# U_I_Meter_TOP.net
KiCad netlist of a schematic drawn in Altium Designer
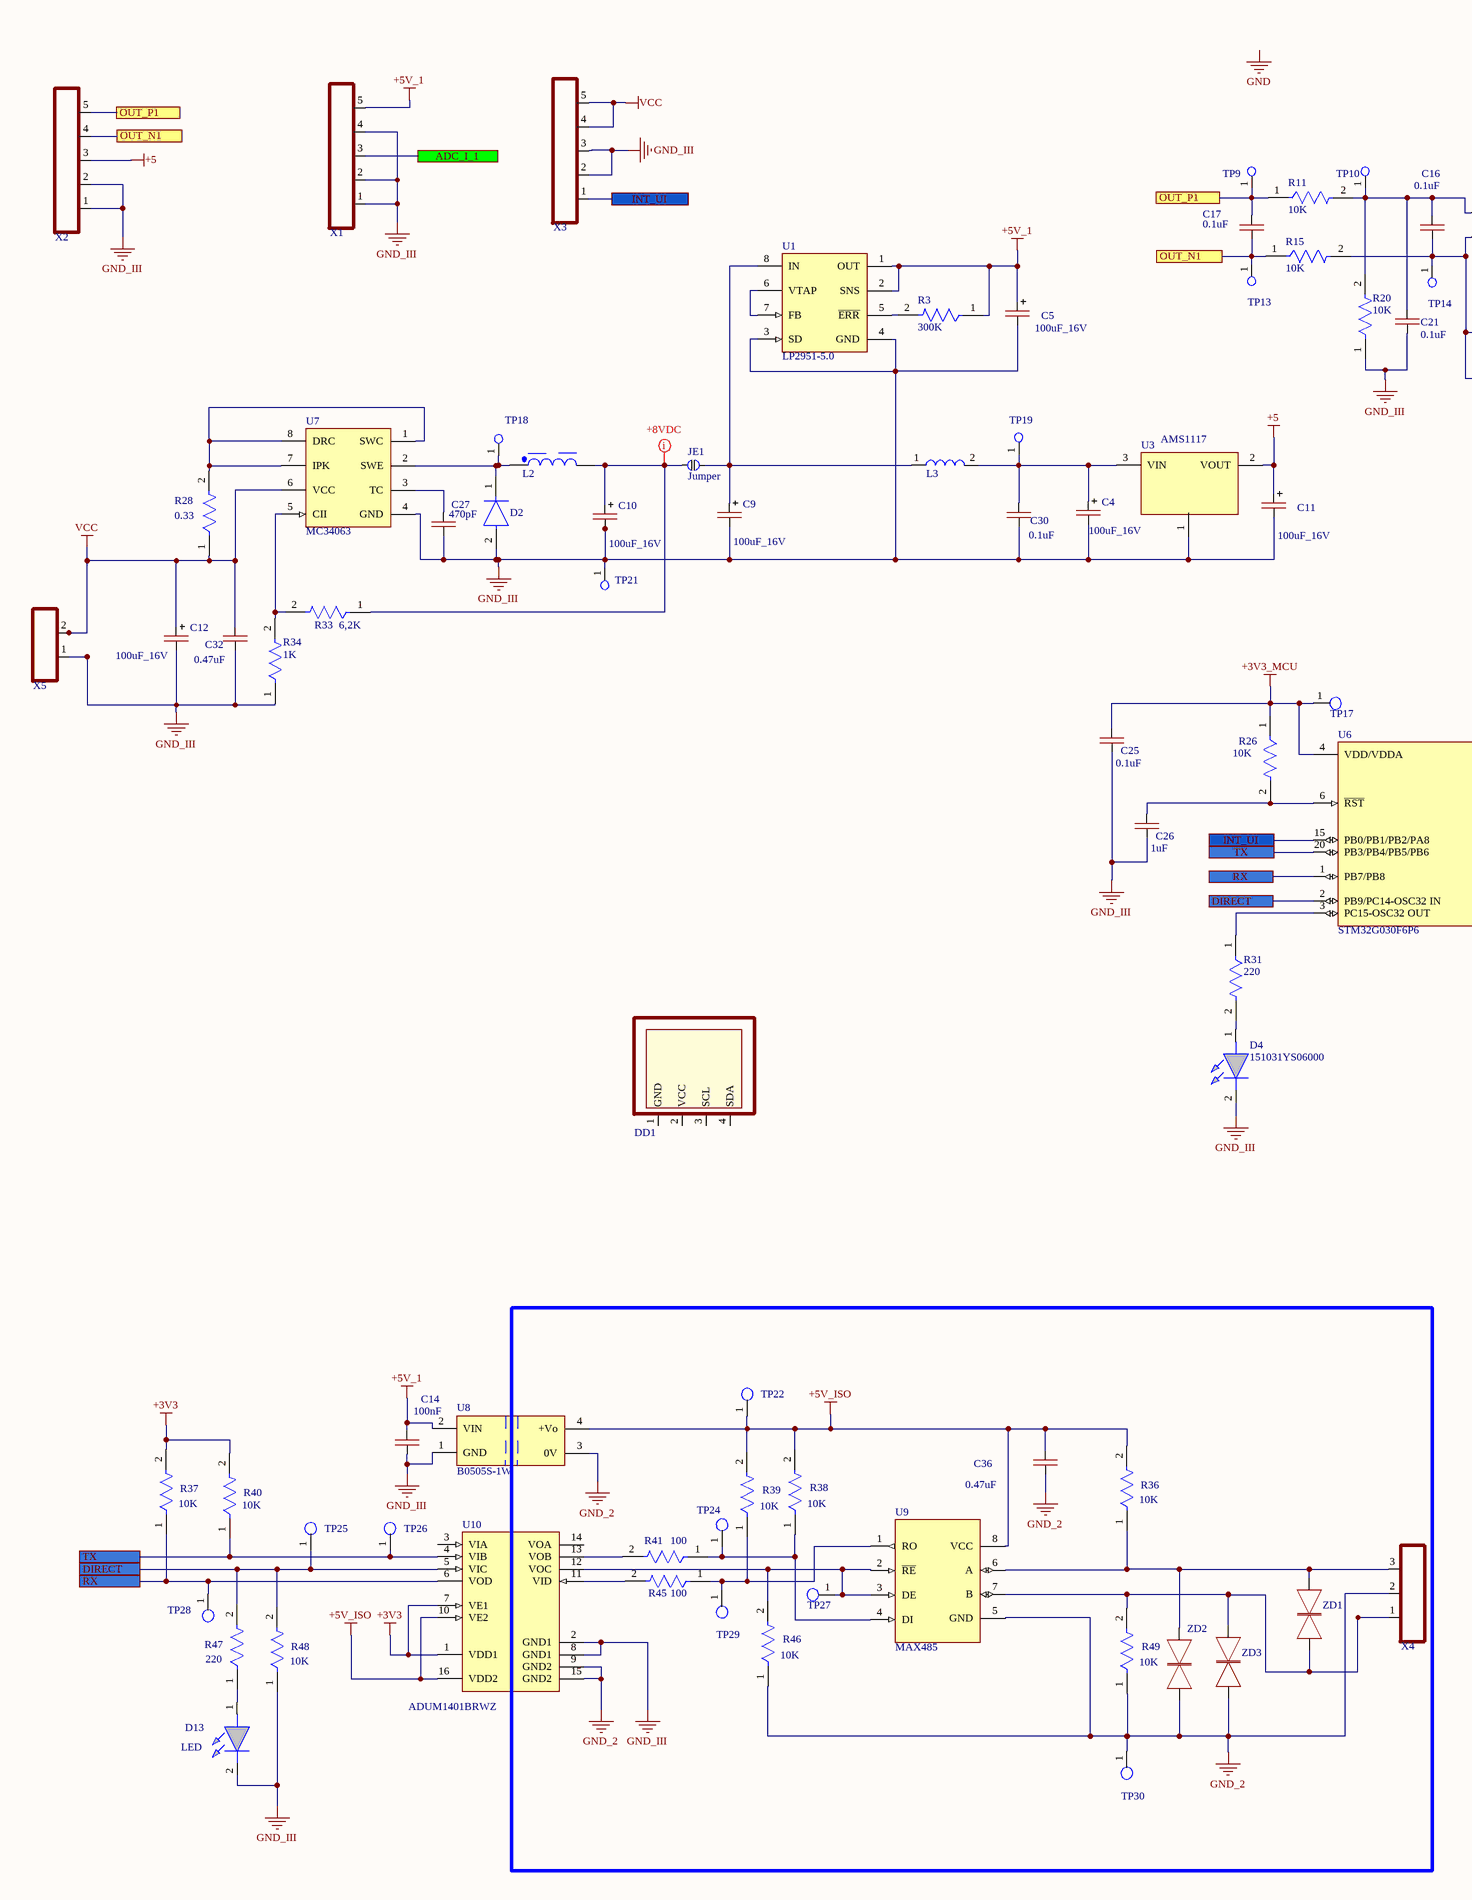
[diagram p0: U_I_Meter_TOP.SchDoc, left]
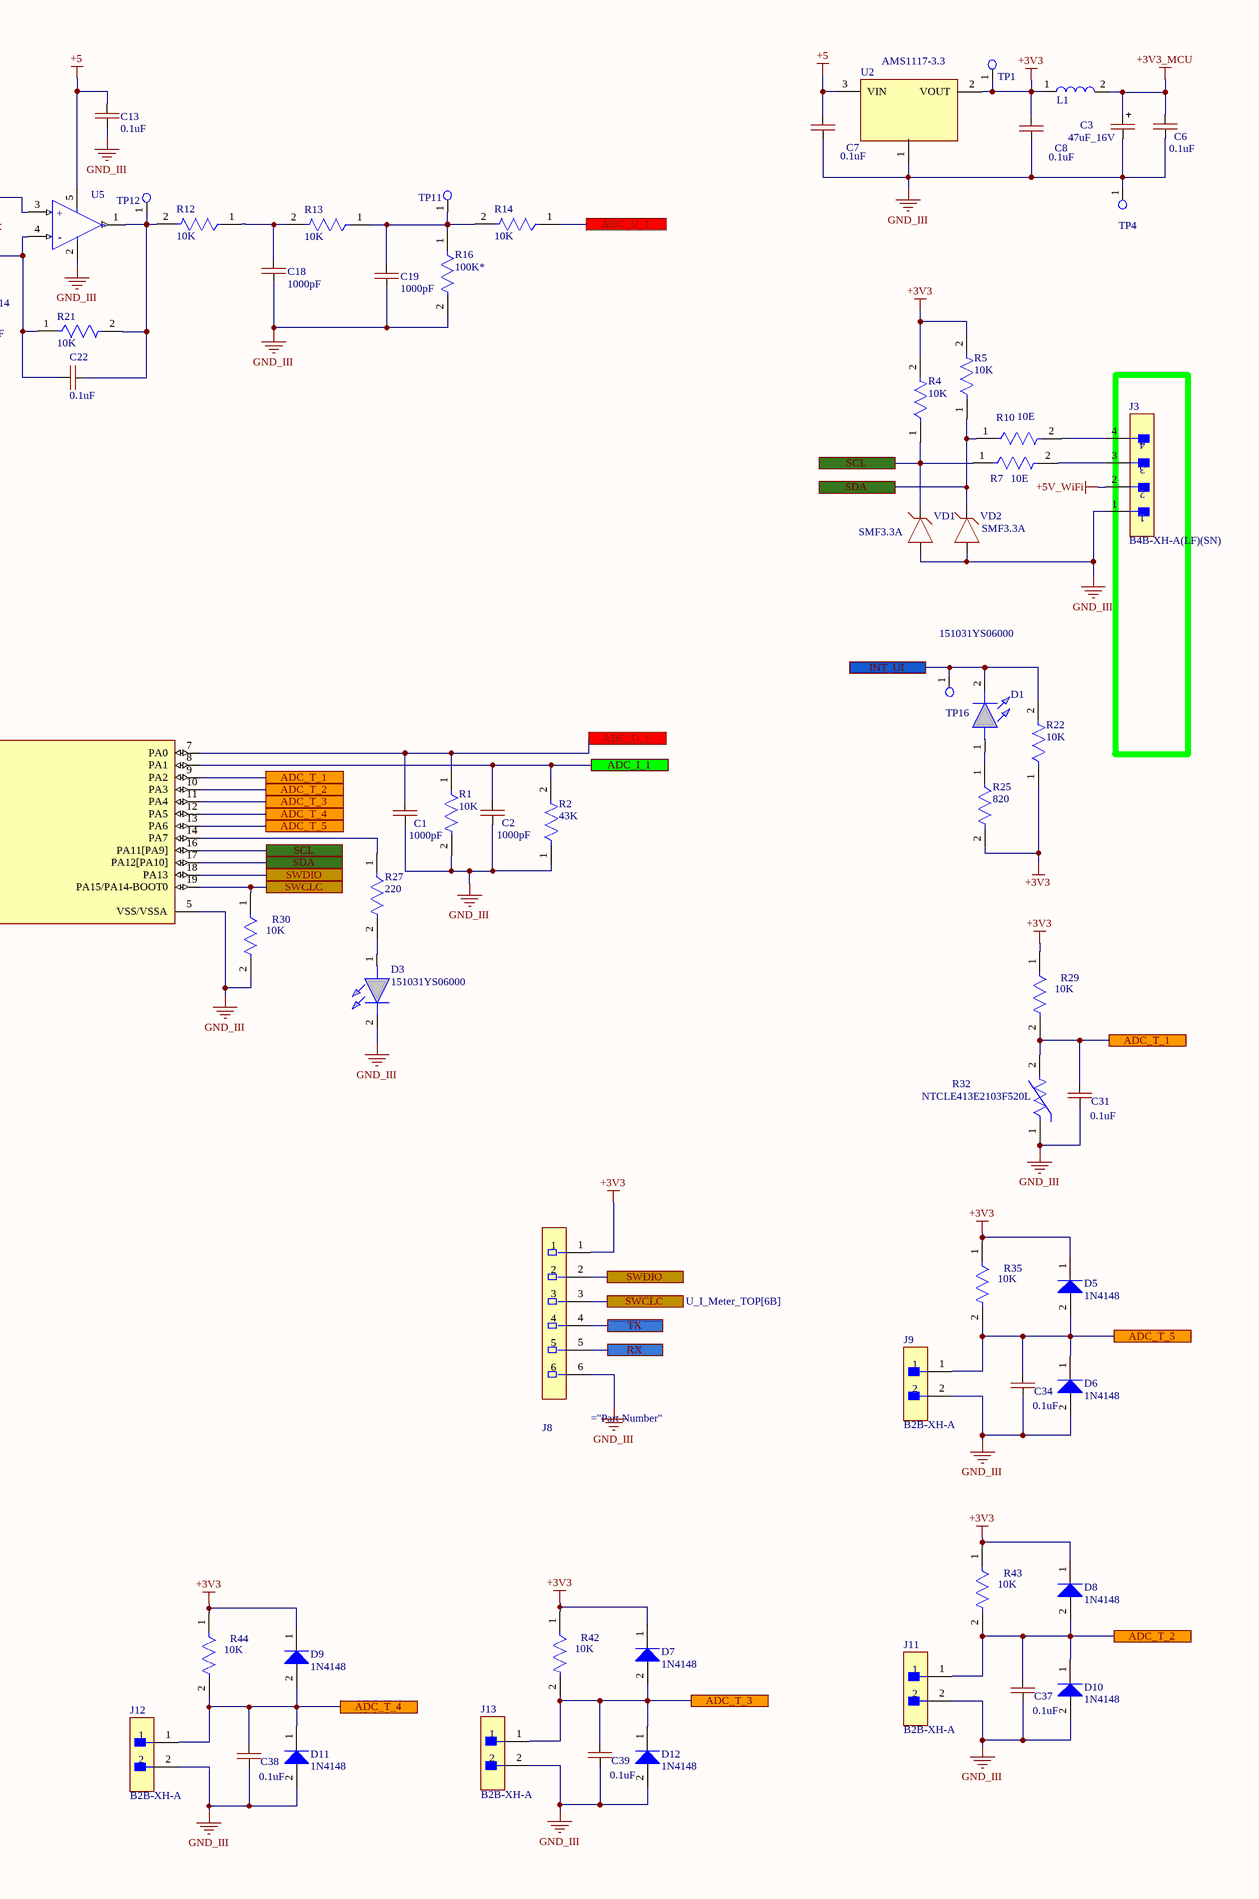
[diagram p1: U_I_Meter_TOP.SchDoc, right]

(export (version "E")
  (design (tool "Eeschema 10.0.6"))
  (components
    (comp (ref "C1")
      (value "1000pF")
      (footprint "CAP-0805")
      (libsource (lib "PASSIVE_COMPONENTS") (part "CAP-NON-POLAR"))
    )
    (comp (ref "C2")
      (value "1000pF")
      (footprint "CAP-0805")
      (libsource (lib "PASSIVE_COMPONENTS") (part "CAP-NON-POLAR"))
    )
    (comp (ref "C3")
      (value "47uF_16V")
      (footprint "CAP-TAN-D")
      (libsource (lib "PASSIVE_COMPONENTS") (part "CAP-POLAR"))
    )
    (comp (ref "C4")
      (value "100uF_16V")
      (footprint "CAP-TAN-D")
      (libsource (lib "PASSIVE_COMPONENTS") (part "CAP_POL_SMD"))
    )
    (comp (ref "C5")
      (value "100uF_16V")
      (footprint "CAP-TAN-D")
      (libsource (lib "PASSIVE_COMPONENTS") (part "CAP_POL_SMD"))
    )
    (comp (ref "C6")
      (value "0.1uF")
      (footprint "CAP-0805")
      (libsource (lib "PASSIVE_COMPONENTS") (part "CAP-NON-POLAR"))
    )
    (comp (ref "C7")
      (value "0.1uF")
      (footprint "CAP-0805")
      (libsource (lib "PASSIVE_COMPONENTS") (part "CAP-NON-POLAR"))
    )
    (comp (ref "C8")
      (value "0.1uF")
      (footprint "CAP-0805")
      (libsource (lib "PASSIVE_COMPONENTS") (part "CAP-NON-POLAR"))
    )
    (comp (ref "C9")
      (value "100uF_16V")
      (footprint "CAP-TAN-D")
      (libsource (lib "PASSIVE_COMPONENTS") (part "CAP_POL_SMD"))
    )
    (comp (ref "C10")
      (value "100uF_16V")
      (footprint "CAP-TAN-D")
      (libsource (lib "PASSIVE_COMPONENTS") (part "CAP_POL_SMD"))
    )
    (comp (ref "C11")
      (value "100uF_16V")
      (footprint "CAP-TAN-D")
      (libsource (lib "PASSIVE_COMPONENTS") (part "CAP_POL_SMD"))
    )
    (comp (ref "C12")
      (value "100uF_16V")
      (footprint "CAP-TAN-D")
      (libsource (lib "PASSIVE_COMPONENTS") (part "CAP_POL_SMD"))
    )
    (comp (ref "C13")
      (value "0.1uF")
      (footprint "CAP-0805")
      (libsource (lib "PASSIVE_COMPONENTS") (part "CAP-NON-POLAR"))
    )
    (comp (ref "C14")
      (value "100nF")
      (footprint "CAP-0805")
      (libsource (lib "PASSIVE_COMPONENTS") (part "CAP-NON-POLAR"))
    )
    (comp (ref "C16")
      (value "0.1uF")
      (footprint "CAP-0805")
      (libsource (lib "PASSIVE_COMPONENTS") (part "CAP-NON-POLAR"))
    )
    (comp (ref "C17")
      (value "0.1uF")
      (footprint "CAP-0805")
      (libsource (lib "PASSIVE_COMPONENTS") (part "CAP-NON-POLAR"))
    )
    (comp (ref "C18")
      (value "1000pF")
      (footprint "CAP-0805")
      (libsource (lib "PASSIVE_COMPONENTS") (part "CAP-NON-POLAR"))
    )
    (comp (ref "C19")
      (value "1000pF")
      (footprint "CAP-0805")
      (libsource (lib "PASSIVE_COMPONENTS") (part "CAP-NON-POLAR"))
    )
    (comp (ref "C21")
      (value "0.1uF")
      (footprint "CAP-0805")
      (libsource (lib "PASSIVE_COMPONENTS") (part "CAP-NON-POLAR"))
    )
    (comp (ref "C22")
      (value "0.1uF")
      (footprint "CAP-0805")
      (libsource (lib "PASSIVE_COMPONENTS") (part "CAP-NON-POLAR"))
    )
    (comp (ref "C25")
      (value "0.1uF")
      (footprint "CAP-0805")
      (libsource (lib "PASSIVE_COMPONENTS") (part "CAP-NON-POLAR"))
    )
    (comp (ref "C26")
      (value "1uF")
      (footprint "CAP-0805")
      (libsource (lib "PASSIVE_COMPONENTS") (part "CAP-NON-POLAR"))
    )
    (comp (ref "C27")
      (value "470pF")
      (footprint "CAP-0805")
      (libsource (lib "PASSIVE_COMPONENTS") (part "CAP-NON-POLAR"))
    )
    (comp (ref "C30")
      (value "0.1uF")
      (footprint "CAP-0805")
      (libsource (lib "PASSIVE_COMPONENTS") (part "CAP-NON-POLAR"))
    )
    (comp (ref "C31")
      (value "0.1uF")
      (footprint "CAP-0805")
      (libsource (lib "PASSIVE_COMPONENTS") (part "CAP-NON-POLAR"))
    )
    (comp (ref "C32")
      (value "0.47uF")
      (footprint "CAP-0805")
      (libsource (lib "PASSIVE_COMPONENTS") (part "CAP-NON-POLAR"))
    )
    (comp (ref "C34")
      (value "0.1uF")
      (footprint "CAP-0805")
      (libsource (lib "PASSIVE_COMPONENTS") (part "CAP-NON-POLAR"))
    )
    (comp (ref "C36")
      (value "0.47uF")
      (footprint "CAP-0805")
      (libsource (lib "PASSIVE_COMPONENTS") (part "CAP-NON-POLAR"))
    )
    (comp (ref "C37")
      (value "0.1uF")
      (footprint "CAP-0805")
      (libsource (lib "PASSIVE_COMPONENTS") (part "CAP-NON-POLAR"))
    )
    (comp (ref "C38")
      (value "0.1uF")
      (footprint "CAP-0805")
      (libsource (lib "PASSIVE_COMPONENTS") (part "CAP-NON-POLAR"))
    )
    (comp (ref "C39")
      (value "0.1uF")
      (footprint "CAP-0805")
      (libsource (lib "PASSIVE_COMPONENTS") (part "CAP-NON-POLAR"))
    )
    (comp (ref "D1")
      (value "151031YS06000")
      (footprint "LED_3mm_BLUE")
      (description "WURTH ELEKTRONIK - 151031YS06000 - LED, Yellow, Through Hole, T-1 (3mm), 30 mA, 2 V, 590 nm")
      (fields (field (name "MOUSER PART NUMBER") "710-151031YS06000"))
      (libsource (lib "Optic-LED") (part "LED"))
    )
    (comp (ref "D2")
      (value "ES1G")
      (footprint "FP-403AE-MFG")
      (description "Ultrafast")
      (libsource (lib "Diodes") (part "ES1G"))
    )
    (comp (ref "D3")
      (value "151031YS06000")
      (footprint "LED_3mm_GREEN")
      (description "WURTH ELEKTRONIK - 151031YS06000 - LED, Yellow, Through Hole, T-1 (3mm), 30 mA, 2 V, 590 nm")
      (fields (field (name "MOUSER PART NUMBER") "710-151031YS06000"))
      (libsource (lib "Optic-LED") (part "LED"))
    )
    (comp (ref "D4")
      (value "151031YS06000")
      (footprint "LED_3mm_RED")
      (description "WURTH ELEKTRONIK - 151031YS06000 - LED, Yellow, Through Hole, T-1 (3mm), 30 mA, 2 V, 590 nm")
      (fields (field (name "MOUSER PART NUMBER") "710-151031YS06000"))
      (libsource (lib "Optic-LED") (part "LED"))
    )
    (comp (ref "D5")
      (value "1N4148")
      (footprint "DIOD-SOD123-2_V")
      (libsource (lib "Diodes") (part "1N4148"))
    )
    (comp (ref "D6")
      (value "1N4148")
      (footprint "DIOD-SOD123-2_V")
      (libsource (lib "Diodes") (part "1N4148"))
    )
    (comp (ref "D7")
      (value "1N4148")
      (footprint "DIOD-SOD123-2_V")
      (libsource (lib "Diodes") (part "1N4148"))
    )
    (comp (ref "D8")
      (value "1N4148")
      (footprint "DIOD-SOD123-2_V")
      (libsource (lib "Diodes") (part "1N4148"))
    )
    (comp (ref "D9")
      (value "1N4148")
      (footprint "DIOD-SOD123-2_V")
      (libsource (lib "Diodes") (part "1N4148"))
    )
    (comp (ref "D10")
      (value "1N4148")
      (footprint "DIOD-SOD123-2_V")
      (libsource (lib "Diodes") (part "1N4148"))
    )
    (comp (ref "D11")
      (value "1N4148")
      (footprint "DIOD-SOD123-2_V")
      (libsource (lib "Diodes") (part "1N4148"))
    )
    (comp (ref "D12")
      (value "1N4148")
      (footprint "DIOD-SOD123-2_V")
      (libsource (lib "Diodes") (part "1N4148"))
    )
    (comp (ref "D13")
      (value "LED")
      (footprint "LED_3mm_BLUE")
      (description "WURTH ELEKTRONIK - 151031YS06000 - LED, Yellow, Through Hole, T-1 (3mm), 30 mA, 2 V, 590 nm")
      (fields
        (field (name "MANUFACTURER_PART_NUMBER") "151031YS06000")
        (field (name "MOUSER PART NUMBER") "710-151031YS06000")
      )
      (libsource (lib "Optic-LED") (part "LED"))
    )
    (comp (ref "DD1")
      (value "OLED_SSD_1306")
      (footprint "OLED_128x64_SSD_1306")
      (libsource (lib "Displays") (part "OLED_SSD_1306"))
    )
    (comp (ref "J3")
      (value "B4B-XH-A(LF)(SN)")
      (footprint "B4B-XH-A")
      (libsource (lib "Connectors") (part "B4B-XH-A(LF)(SN)"))
    )
    (comp (ref "J8")
      (value "SWR25X-NRTC-S06-ST-BA")
      (footprint "Sullins_SWR25X-NRTC-S06-ST-BA_MFG")
      (libsource (lib "Conn_Sullins_SWR25X-NRTC-S06-ST-BA_eec") (part "SWR25X-NRTC-S06-ST-BA"))
    )
    (comp (ref "J9")
      (value "B2B-XH-A")
      (footprint "B2B-XH-A")
      (libsource (lib "Connectors") (part "B2B-XH-A"))
    )
    (comp (ref "J11")
      (value "B2B-XH-A")
      (footprint "B2B-XH-A")
      (libsource (lib "Connectors") (part "B2B-XH-A"))
    )
    (comp (ref "J12")
      (value "B2B-XH-A")
      (footprint "B2B-XH-A")
      (libsource (lib "Connectors") (part "B2B-XH-A"))
    )
    (comp (ref "J13")
      (value "B2B-XH-A")
      (footprint "B2B-XH-A")
      (libsource (lib "Connectors") (part "B2B-XH-A"))
    )
    (comp (ref "JE1") (value "Jumper") (footprint "JE") (libsource (lib "Connectors") (part "JE")))
    (comp (ref "L1")
      (value "Coil")
      (footprint "Coil_4.5x4.5_mm")
      (libsource (lib "Transformers") (part "Coil"))
    )
    (comp (ref "L2")
      (value "3.3µH, 4A")
      (footprint "WE-PD2_5848")
      (description "WE-PD2 SMT Power Inductor, size 5848, 3.3µH, 4A, 0.06Ω")
      (fields
        (field (name "MANUFACTURER PART NUMBER") "744774033")
        (field (name "MANUFACTURER") "Wurth Elektronik")
      )
      (libsource (lib "WE-PD2 (rev22d)") (part "744774033"))
    )
    (comp (ref "L3")
      (value "Coil")
      (footprint "Coil_4.5x4.5_mm")
      (libsource (lib "Transformers") (part "Coil"))
    )
    (comp (ref "R1")
      (value "10K")
      (footprint "RES-0805")
      (libsource (lib "PASSIVE_COMPONENTS") (part "RES-CONST"))
    )
    (comp (ref "R2")
      (value "43K")
      (footprint "RES-0805")
      (libsource (lib "PASSIVE_COMPONENTS") (part "RES-CONST"))
    )
    (comp (ref "R3")
      (value "300K")
      (footprint "RES-0805")
      (libsource (lib "PASSIVE_COMPONENTS") (part "RES-CONST"))
    )
    (comp (ref "R4")
      (value "10K")
      (footprint "RES-0805")
      (libsource (lib "PASSIVE_COMPONENTS") (part "RES-CONST"))
    )
    (comp (ref "R5")
      (value "10K")
      (footprint "RES-0805")
      (libsource (lib "PASSIVE_COMPONENTS") (part "RES-CONST"))
    )
    (comp (ref "R7")
      (value "10E")
      (footprint "RES-0805")
      (libsource (lib "PASSIVE_COMPONENTS") (part "RES-CONST"))
    )
    (comp (ref "R10")
      (value "10E")
      (footprint "RES-0805")
      (libsource (lib "PASSIVE_COMPONENTS") (part "RES-CONST"))
    )
    (comp (ref "R11")
      (value "10K")
      (footprint "RES-0805")
      (libsource (lib "PASSIVE_COMPONENTS") (part "RES-CONST"))
    )
    (comp (ref "R12")
      (value "10K")
      (footprint "RES-0805")
      (libsource (lib "PASSIVE_COMPONENTS") (part "RES-CONST"))
    )
    (comp (ref "R13")
      (value "10K")
      (footprint "RES-0805")
      (libsource (lib "PASSIVE_COMPONENTS") (part "RES-CONST"))
    )
    (comp (ref "R14")
      (value "10K")
      (footprint "RES-0805")
      (libsource (lib "PASSIVE_COMPONENTS") (part "RES-CONST"))
    )
    (comp (ref "R15")
      (value "10K")
      (footprint "RES-0805")
      (libsource (lib "PASSIVE_COMPONENTS") (part "RES-CONST"))
    )
    (comp (ref "R16")
      (value "100K*")
      (footprint "RES-0805")
      (libsource (lib "PASSIVE_COMPONENTS") (part "RES-CONST"))
    )
    (comp (ref "R20")
      (value "10K")
      (footprint "RES-0805")
      (libsource (lib "PASSIVE_COMPONENTS") (part "RES-CONST"))
    )
    (comp (ref "R21")
      (value "10K")
      (footprint "RES-0805")
      (libsource (lib "PASSIVE_COMPONENTS") (part "RES-CONST"))
    )
    (comp (ref "R22")
      (value "10K")
      (footprint "RES-0805")
      (libsource (lib "PASSIVE_COMPONENTS") (part "RES-CONST"))
    )
    (comp (ref "R25")
      (value "820")
      (footprint "RES-0805")
      (description "220")
      (libsource (lib "PASSIVE_COMPONENTS") (part "RES-CONST"))
    )
    (comp (ref "R26")
      (value "10K")
      (footprint "RES-0805")
      (libsource (lib "PASSIVE_COMPONENTS") (part "RES-CONST"))
    )
    (comp (ref "R27")
      (value "220")
      (footprint "RES-0805")
      (libsource (lib "PASSIVE_COMPONENTS") (part "RES-CONST"))
    )
    (comp (ref "R28")
      (value "0.33")
      (footprint "RES-1206")
      (libsource (lib "PASSIVE_COMPONENTS") (part "RES-CONST"))
    )
    (comp (ref "R29")
      (value "10K")
      (footprint "RES-0805")
      (libsource (lib "PASSIVE_COMPONENTS") (part "RES-CONST"))
    )
    (comp (ref "R30")
      (value "10K")
      (footprint "RES-0805")
      (libsource (lib "PASSIVE_COMPONENTS") (part "RES-CONST"))
    )
    (comp (ref "R31")
      (value "220")
      (footprint "RES-0805")
      (libsource (lib "PASSIVE_COMPONENTS") (part "RES-CONST"))
    )
    (comp (ref "R32")
      (value "NTCLE413E2103F520L")
      (footprint "FP-NTCLE413E2103F520L-MFG")
      (description "THERMISTOR NTC 10KOHM 3435K BEAD")
      (fields (field (name "TOLERANCE") "1%"))
      (libsource (lib "Altium Content Vault") (part "3b148a6ebabc5fb4d708a66c052d352"))
    )
    (comp (ref "R33")
      (value "6,2K")
      (footprint "RES-0805")
      (description "10K")
      (libsource (lib "PASSIVE_COMPONENTS") (part "RES-CONST"))
    )
    (comp (ref "R34")
      (value "1K")
      (footprint "RES-0805")
      (description "1.2K")
      (libsource (lib "PASSIVE_COMPONENTS") (part "RES-CONST"))
    )
    (comp (ref "R35")
      (value "10K")
      (footprint "RES-0805")
      (libsource (lib "PASSIVE_COMPONENTS") (part "RES-CONST"))
    )
    (comp (ref "R36")
      (value "10K")
      (footprint "RES-0805")
      (libsource (lib "PASSIVE_COMPONENTS") (part "RES-CONST"))
    )
    (comp (ref "R37")
      (value "10K")
      (footprint "RES-0805")
      (libsource (lib "PASSIVE_COMPONENTS") (part "RES-CONST"))
    )
    (comp (ref "R38")
      (value "10K")
      (footprint "RES-0805")
      (libsource (lib "PASSIVE_COMPONENTS") (part "RES-CONST"))
    )
    (comp (ref "R39")
      (value "10K")
      (footprint "RES-0805")
      (libsource (lib "PASSIVE_COMPONENTS") (part "RES-CONST"))
    )
    (comp (ref "R40")
      (value "10K")
      (footprint "RES-0805")
      (libsource (lib "PASSIVE_COMPONENTS") (part "RES-CONST"))
    )
    (comp (ref "R41")
      (value "100")
      (footprint "RES-0805")
      (libsource (lib "PASSIVE_COMPONENTS") (part "RES-CONST"))
    )
    (comp (ref "R42")
      (value "10K")
      (footprint "RES-0805")
      (libsource (lib "PASSIVE_COMPONENTS") (part "RES-CONST"))
    )
    (comp (ref "R43")
      (value "10K")
      (footprint "RES-0805")
      (libsource (lib "PASSIVE_COMPONENTS") (part "RES-CONST"))
    )
    (comp (ref "R44")
      (value "10K")
      (footprint "RES-0805")
      (libsource (lib "PASSIVE_COMPONENTS") (part "RES-CONST"))
    )
    (comp (ref "R45")
      (value "100")
      (footprint "RES-0805")
      (libsource (lib "PASSIVE_COMPONENTS") (part "RES-CONST"))
    )
    (comp (ref "R46")
      (value "10K")
      (footprint "RES-0805")
      (libsource (lib "PASSIVE_COMPONENTS") (part "RES-CONST"))
    )
    (comp (ref "R47")
      (value "220")
      (footprint "RES-0805")
      (libsource (lib "PASSIVE_COMPONENTS") (part "RES-CONST"))
    )
    (comp (ref "R48")
      (value "10K")
      (footprint "RES-0805")
      (libsource (lib "PASSIVE_COMPONENTS") (part "RES-CONST"))
    )
    (comp (ref "R49")
      (value "10K")
      (footprint "RES-0805")
      (libsource (lib "PASSIVE_COMPONENTS") (part "RES-CONST"))
    )
    (comp (ref "TP1")
      (value "Test_Point_PCB")
      (footprint "Test_Point")
      (description "Test_Point")
      (libsource (lib "Connectors") (part "TP_PCB?"))
    )
    (comp (ref "TP4")
      (value "Test_Point_PCB")
      (footprint "Pin_Test_Point(Pink)")
      (description "Test_Point")
      (libsource (lib "Connectors") (part "TP_PCB?"))
    )
    (comp (ref "TP9")
      (value "Test_Point_PCB")
      (footprint "Test_Point")
      (description "Test_Point")
      (libsource (lib "Connectors") (part "TP_PCB?"))
    )
    (comp (ref "TP10")
      (value "Test_Point_PCB")
      (footprint "Test_Point")
      (description "Test_Point")
      (libsource (lib "Connectors") (part "TP_PCB?"))
    )
    (comp (ref "TP11")
      (value "Test_Point_PCB")
      (footprint "Test_Point")
      (description "Test_Point")
      (libsource (lib "Connectors") (part "TP_PCB?"))
    )
    (comp (ref "TP12")
      (value "Test_Point_PCB")
      (footprint "Test_Point")
      (description "Test_Point")
      (libsource (lib "Connectors") (part "TP_PCB?"))
    )
    (comp (ref "TP13")
      (value "Test_Point_PCB")
      (footprint "Test_Point")
      (description "Test_Point")
      (libsource (lib "Connectors") (part "TP_PCB?"))
    )
    (comp (ref "TP14")
      (value "Test_Point_PCB")
      (footprint "Test_Point")
      (description "Test_Point")
      (libsource (lib "Connectors") (part "TP_PCB?"))
    )
    (comp (ref "TP16")
      (value "Test_Point_PCB")
      (footprint "Test_Point")
      (description "Test_Point")
      (libsource (lib "Connectors") (part "TP_PCB?"))
    )
    (comp (ref "TP17")
      (value "~")
      (footprint "Test_Point")
      (description "Test_Point")
      (libsource (lib "") (part "TP_PCB?_1"))
    )
    (comp (ref "TP18")
      (value "Test_Point_PCB")
      (footprint "Test_Point")
      (description "Test_Point")
      (libsource (lib "Connectors") (part "TP_PCB?"))
    )
    (comp (ref "TP19")
      (value "Test_Point_PCB")
      (footprint "Test_Point")
      (description "Test_Point")
      (libsource (lib "Connectors") (part "TP_PCB?"))
    )
    (comp (ref "TP21")
      (value "Test_Point_PCB")
      (footprint "Pin_Test_Point(Orange)")
      (description "Test_Point")
      (libsource (lib "Connectors") (part "TP_PCB?"))
    )
    (comp (ref "TP22")
      (value "Test_Point_PCB")
      (footprint "Test_Point")
      (description "Test_Point")
      (libsource (lib "Test_Point") (part "TP_PCB?"))
    )
    (comp (ref "TP24")
      (value "Test_Point_PCB")
      (footprint "Test_Point")
      (description "Test_Point")
      (libsource (lib "Test_Point") (part "TP_PCB?"))
    )
    (comp (ref "TP25")
      (value "Test_Point_PCB")
      (footprint "Test_Point")
      (description "Test_Point")
      (libsource (lib "Test_Point") (part "TP_PCB?"))
    )
    (comp (ref "TP26")
      (value "Test_Point_PCB")
      (footprint "Test_Point")
      (description "Test_Point")
      (libsource (lib "Test_Point") (part "TP_PCB?"))
    )
    (comp (ref "TP27")
      (value "Test_Point_PCB")
      (footprint "Test_Point")
      (description "Test_Point")
      (libsource (lib "Test_Point") (part "TP_PCB?"))
    )
    (comp (ref "TP28")
      (value "Test_Point_PCB")
      (footprint "Test_Point")
      (description "Test_Point")
      (libsource (lib "Test_Point") (part "TP_PCB?"))
    )
    (comp (ref "TP29")
      (value "~")
      (footprint "Test_Point")
      (description "Test_Point")
      (libsource (lib "") (part "TP_PCB?_1"))
    )
    (comp (ref "TP30")
      (value "Test_Point_PCB")
      (footprint "Test_Point")
      (description "Test_Point")
      (libsource (lib "Test_Point") (part "TP_PCB?"))
    )
    (comp (ref "U1")
      (value "LP2951-5.0")
      (footprint "SOIC-8_L")
      (libsource (lib "Integrated_Circuts") (part "LP2951-3.3"))
    )
    (comp (ref "U2")
      (value "AMS1117-3.3")
      (footprint "SOT-223")
      (libsource (lib "Integrated_Circuts") (part "AMS1117"))
    )
    (comp (ref "U3")
      (value "AMS1117")
      (footprint "SOT-89")
      (libsource (lib "Integrated_Circuts") (part "AMS1117"))
    )
    (comp (ref "U5")
      (value "~")
      (footprint "SOT-23-5")
      (description "IC OPAMP GP 1 CIRCUIT SOT23-5")
      (fields (field (name "VOLTAGE") "6V"))
      (libsource (lib "Integrated_Circuts") (part "MCP6001T"))
    )
    (comp (ref "U6")
      (value "STM32G030F6P6")
      (footprint "FP-TSSOP20-YA-IPC_A")
      (description "SOIC-20")
      (libsource (lib "Integrated_Circuts") (part "STM32G030F6P6"))
    )
    (comp (ref "U7")
      (value "MC34063")
      (footprint "SOIC-8_M")
      (libsource (lib "Integrated_Circuts") (part "MC34063"))
    )
    (comp (ref "U8")
      (value "B0505S-1W")
      (footprint "B0505S-1W")
      (libsource (lib "Integrated_Circuts") (part "B0505S-1W"))
    )
    (comp (ref "U9")
      (value "MAX485")
      (footprint "SOIC-8-MFG")
      (libsource (lib "Integrated_Circuts") (part "MAX485"))
    )
    (comp (ref "U10")
      (value "ADUM1401BRWZ")
      (footprint "ADI-RW-16_M")
      (fields (field (name "MANUFACTURER") "Analog Devices"))
      (libsource (lib "Altium Content Vault") (part "ADI-ADUMX4X1-16"))
    )
    (comp (ref "VD1")
      (value "SMF3.3A")
      (footprint "SMF3.3A")
      (libsource (lib "Diodes") (part "ESD_Unidirect"))
    )
    (comp (ref "VD2")
      (value "SMF3.3A")
      (footprint "SMF3.3A")
      (libsource (lib "Diodes") (part "ESD_Unidirect"))
    )
    (comp (ref "X1")
      (value "CONN-5-PIN")
      (footprint "CONN-PLS-5-2.54_2")
      (libsource (lib "PLS-5__") (part "CONN-5-PIN"))
    )
    (comp (ref "X2")
      (value "CONN-5-PIN")
      (footprint "CONN-PLS-5-2.54_2")
      (libsource (lib "PLS-5__") (part "CONN-5-PIN"))
    )
    (comp (ref "X3")
      (value "CONN-5-PIN")
      (footprint "CONN-PLS-5-2.54_2")
      (libsource (lib "PLS-5__") (part "CONN-5-PIN"))
    )
    (comp (ref "X4")
      (value "CONN-3-PIN")
      (footprint "691305340003")
      (libsource (lib "691305340003") (part "CONN-3-PIN"))
    )
    (comp (ref "X5")
      (value "CONN-2-PIN")
      (footprint "691305340002")
      (libsource (lib "691305340003") (part "CONN-2-PIN"))
    )
    (comp (ref "ZD1")
      (value "P6SMB16CA")
      (footprint "DO-214AA")
      (libsource (lib "P6SMB16CA") (part "P6SMB16CA"))
    )
    (comp (ref "ZD2")
      (value "P6SMB16CA")
      (footprint "DO-214AA")
      (libsource (lib "P6SMB16CA") (part "P6SMB16CA"))
    )
    (comp (ref "ZD3")
      (value "P6SMB16CA")
      (footprint "DO-214AA")
      (libsource (lib "P6SMB16CA") (part "P6SMB16CA"))
    )
  )
  (nets
    (net (code "1") (name "+3V3") (class "Default")
      (node (ref "C8") (pin "2") (pinfunction "2_2") (pintype "passive"))
      (node (ref "D5") (pin "1") (pinfunction "K_1") (pintype "passive"))
      (node (ref "D7") (pin "1") (pinfunction "K_1") (pintype "passive"))
      (node (ref "D8") (pin "1") (pinfunction "K_1") (pintype "passive"))
      (node (ref "D9") (pin "1") (pinfunction "K_1") (pintype "passive"))
      (node (ref "J8") (pin "1") (pinfunction "1_1") (pintype "passive"))
      (node (ref "L1") (pin "1") (pinfunction "1_1") (pintype "passive"))
      (node (ref "R22") (pin "1") (pinfunction "1_1") (pintype "passive"))
      (node (ref "R25") (pin "2") (pinfunction "2_2") (pintype "passive"))
      (node (ref "R29") (pin "1") (pinfunction "1_1") (pintype "passive"))
      (node (ref "R35") (pin "1") (pinfunction "1_1") (pintype "passive"))
      (node (ref "R37") (pin "2") (pinfunction "2_2") (pintype "passive"))
      (node (ref "R4") (pin "2") (pinfunction "2_2") (pintype "passive"))
      (node (ref "R40") (pin "2") (pinfunction "2_2") (pintype "passive"))
      (node (ref "R42") (pin "1") (pinfunction "1_1") (pintype "passive"))
      (node (ref "R43") (pin "1") (pinfunction "1_1") (pintype "passive"))
      (node (ref "R44") (pin "1") (pinfunction "1_1") (pintype "passive"))
      (node (ref "R5") (pin "2") (pinfunction "2_2") (pintype "passive"))
      (node (ref "TP1") (pin "1") (pinfunction "G9_1") (pintype "passive"))
      (node (ref "U10") (pin "1") (pinfunction "VDD1_1") (pintype "power_in"))
      (node (ref "U10") (pin "7") (pinfunction "VE1_7") (pintype "input"))
      (node (ref "U2") (pin "2") (pinfunction "VOUT_2") (pintype "passive"))
    )
    (net (code "2") (name "+3V3_MCU") (class "Default")
      (node (ref "C25") (pin "2") (pinfunction "2_2") (pintype "passive"))
      (node (ref "C3") (pin "1") (pinfunction "+_1") (pintype "passive"))
      (node (ref "C6") (pin "2") (pinfunction "2_2") (pintype "passive"))
      (node (ref "L1") (pin "2") (pinfunction "2_2") (pintype "passive"))
      (node (ref "R26") (pin "1") (pinfunction "1_1") (pintype "passive"))
      (node (ref "TP17") (pin "1") (pinfunction "G9_1") (pintype "passive"))
      (node (ref "U6") (pin "4") (pinfunction "VDD/VDDA_4") (pintype "power_in"))
    )
    (net (code "3") (name "+5") (class "Default")
      (node (ref "C11") (pin "1") (pinfunction "+_1") (pintype "passive"))
      (node (ref "C13") (pin "2") (pinfunction "2_2") (pintype "passive"))
      (node (ref "C7") (pin "2") (pinfunction "2_2") (pintype "passive"))
      (node (ref "U2") (pin "3") (pinfunction "VIN_3") (pintype "power_in"))
      (node (ref "U3") (pin "2") (pinfunction "VOUT_2") (pintype "passive"))
      (node (ref "U5") (pin "5") (pinfunction "VDD_5") (pintype "power_in"))
      (node (ref "X2") (pin "3") (pinfunction "3_3") (pintype "passive"))
    )
    (net (code "4") (name "+5V_1") (class "Default")
      (node (ref "C14") (pin "2") (pinfunction "2_2") (pintype "passive"))
      (node (ref "C5") (pin "1") (pinfunction "+_1") (pintype "passive"))
      (node (ref "R3") (pin "1") (pinfunction "1_1") (pintype "passive"))
      (node (ref "U1") (pin "1") (pinfunction "OUT_1") (pintype "power_in"))
      (node (ref "U1") (pin "2") (pinfunction "SNS_2") (pintype "passive"))
      (node (ref "U8") (pin "2") (pinfunction "VIN_2") (pintype "power_in"))
      (node (ref "X1") (pin "5") (pinfunction "5_5") (pintype "passive"))
    )
    (net (code "5") (name "+5V_ISO") (class "Default")
      (node (ref "C36") (pin "1") (pinfunction "1_1") (pintype "passive"))
      (node (ref "R36") (pin "2") (pinfunction "2_2") (pintype "passive"))
      (node (ref "R38") (pin "2") (pinfunction "2_2") (pintype "passive"))
      (node (ref "R39") (pin "2") (pinfunction "2_2") (pintype "passive"))
      (node (ref "TP22") (pin "1") (pinfunction "G9_1") (pintype "passive"))
      (node (ref "U10") (pin "10") (pinfunction "VE2_10") (pintype "input"))
      (node (ref "U10") (pin "16") (pinfunction "VDD2_16") (pintype "power_in"))
      (node (ref "U8") (pin "4") (pinfunction "+Vo_4") (pintype "power_in"))
      (node (ref "U9") (pin "8") (pinfunction "VCC_8") (pintype "power_in"))
    )
    (net (code "6") (name "+5V_WiFi") (class "Default")
      (node (ref "J3") (pin "2") (pinfunction "2_2") (pintype "passive"))
    )
    (net (code "7") (name "/ADC_I_1") (class "Default")
      (node (ref "C2") (pin "2") (pinfunction "2_2") (pintype "passive"))
      (node (ref "R2") (pin "2") (pinfunction "2_2") (pintype "passive"))
      (node (ref "U6") (pin "8") (pinfunction "PA1_8") (pintype "bidirectional"))
      (node (ref "X1") (pin "3") (pinfunction "3_3") (pintype "passive"))
    )
    (net (code "8") (name "/ADC_T_1") (class "Default")
      (node (ref "C31") (pin "2") (pinfunction "2_2") (pintype "passive"))
      (node (ref "R29") (pin "2") (pinfunction "2_2") (pintype "passive"))
      (node (ref "R32") (pin "2") (pinfunction "2_2") (pintype "passive"))
      (node (ref "U6") (pin "9") (pinfunction "PA2_9") (pintype "bidirectional"))
    )
    (net (code "9") (name "/ADC_T_2") (class "Default")
      (node (ref "C37") (pin "2") (pinfunction "2_2") (pintype "passive"))
      (node (ref "D10") (pin "1") (pinfunction "K_1") (pintype "passive"))
      (node (ref "D8") (pin "2") (pinfunction "A_2") (pintype "passive"))
      (node (ref "J11") (pin "1") (pinfunction "1_1") (pintype "passive"))
      (node (ref "R43") (pin "2") (pinfunction "2_2") (pintype "passive"))
      (node (ref "U6") (pin "10") (pinfunction "PA3_10") (pintype "bidirectional"))
    )
    (net (code "10") (name "/ADC_T_3") (class "Default")
      (node (ref "C39") (pin "2") (pinfunction "2_2") (pintype "passive"))
      (node (ref "D12") (pin "1") (pinfunction "K_1") (pintype "passive"))
      (node (ref "D7") (pin "2") (pinfunction "A_2") (pintype "passive"))
      (node (ref "J13") (pin "1") (pinfunction "1_1") (pintype "passive"))
      (node (ref "R42") (pin "2") (pinfunction "2_2") (pintype "passive"))
      (node (ref "U6") (pin "11") (pinfunction "PA4_11") (pintype "bidirectional"))
    )
    (net (code "11") (name "/ADC_T_4") (class "Default")
      (node (ref "C38") (pin "2") (pinfunction "2_2") (pintype "passive"))
      (node (ref "D11") (pin "1") (pinfunction "K_1") (pintype "passive"))
      (node (ref "D9") (pin "2") (pinfunction "A_2") (pintype "passive"))
      (node (ref "J12") (pin "1") (pinfunction "1_1") (pintype "passive"))
      (node (ref "R44") (pin "2") (pinfunction "2_2") (pintype "passive"))
      (node (ref "U6") (pin "12") (pinfunction "PA5_12") (pintype "bidirectional"))
    )
    (net (code "12") (name "/ADC_T_5") (class "Default")
      (node (ref "C34") (pin "2") (pinfunction "2_2") (pintype "passive"))
      (node (ref "D5") (pin "2") (pinfunction "A_2") (pintype "passive"))
      (node (ref "D6") (pin "1") (pinfunction "K_1") (pintype "passive"))
      (node (ref "J9") (pin "1") (pinfunction "1_1") (pintype "passive"))
      (node (ref "R35") (pin "2") (pinfunction "2_2") (pintype "passive"))
      (node (ref "U6") (pin "13") (pinfunction "PA6_13") (pintype "bidirectional"))
    )
    (net (code "13") (name "/ADC_U_1") (class "Default")
      (node (ref "C1") (pin "2") (pinfunction "2_2") (pintype "passive"))
      (node (ref "R1") (pin "1") (pinfunction "1_1") (pintype "passive"))
      (node (ref "R14") (pin "1") (pinfunction "1_1") (pintype "passive"))
      (node (ref "U6") (pin "7") (pinfunction "PA0_7") (pintype "bidirectional"))
    )
    (net (code "14") (name "/DIRECT") (class "Default")
      (node (ref "R47") (pin "2") (pinfunction "2_2") (pintype "passive"))
      (node (ref "R48") (pin "2") (pinfunction "2_2") (pintype "passive"))
      (node (ref "TP25") (pin "1") (pinfunction "G9_1") (pintype "passive"))
      (node (ref "U10") (pin "5") (pinfunction "VIC_5") (pintype "input"))
      (node (ref "U6") (pin "2") (pinfunction "PB9/PC14-OSC32_IN_2") (pintype "bidirectional"))
    )
    (net (code "15") (name "/INT_UI") (class "Default")
      (node (ref "D1") (pin "2") (pinfunction "K_2") (pintype "passive"))
      (node (ref "R22") (pin "2") (pinfunction "2_2") (pintype "passive"))
      (node (ref "TP16") (pin "1") (pinfunction "G9_1") (pintype "passive"))
      (node (ref "U6") (pin "15") (pinfunction "PB0/PB1/PB2/PA8_15") (pintype "bidirectional"))
      (node (ref "X3") (pin "1") (pinfunction "1_1") (pintype "passive"))
    )
    (net (code "16") (name "/OUT_N1") (class "Default")
      (node (ref "C17") (pin "1") (pinfunction "1_1") (pintype "passive"))
      (node (ref "R15") (pin "1") (pinfunction "1_1") (pintype "passive"))
      (node (ref "TP13") (pin "1") (pinfunction "G9_1") (pintype "passive"))
      (node (ref "X2") (pin "4") (pinfunction "4_4") (pintype "passive"))
    )
    (net (code "17") (name "/OUT_P1") (class "Default")
      (node (ref "C17") (pin "2") (pinfunction "2_2") (pintype "passive"))
      (node (ref "R11") (pin "1") (pinfunction "1_1") (pintype "passive"))
      (node (ref "TP9") (pin "1") (pinfunction "G9_1") (pintype "passive"))
      (node (ref "X2") (pin "5") (pinfunction "5_5") (pintype "passive"))
    )
    (net (code "18") (name "/RX") (class "Default")
      (node (ref "J8") (pin "5") (pinfunction "5_5") (pintype "passive"))
      (node (ref "R37") (pin "1") (pinfunction "1_1") (pintype "passive"))
      (node (ref "TP28") (pin "1") (pinfunction "G9_1") (pintype "passive"))
      (node (ref "U10") (pin "6") (pinfunction "VOD_6") (pintype "tri_state"))
      (node (ref "U6") (pin "1") (pinfunction "PB7/PB8_1") (pintype "bidirectional"))
    )
    (net (code "19") (name "/SCL") (class "Default")
      (node (ref "R4") (pin "1") (pinfunction "1_1") (pintype "passive"))
      (node (ref "R7") (pin "1") (pinfunction "1_1") (pintype "passive"))
      (node (ref "U6") (pin "16") (pinfunction "PA11[PA9]_16") (pintype "bidirectional"))
      (node (ref "VD1") (pin "2") (pinfunction "C_2") (pintype "passive"))
    )
    (net (code "20") (name "/SDA") (class "Default")
      (node (ref "R10") (pin "1") (pinfunction "1_1") (pintype "passive"))
      (node (ref "R5") (pin "1") (pinfunction "1_1") (pintype "passive"))
      (node (ref "U6") (pin "17") (pinfunction "PA12[PA10]_17") (pintype "bidirectional"))
      (node (ref "VD2") (pin "2") (pinfunction "C_2") (pintype "passive"))
    )
    (net (code "21") (name "/SWCLC") (class "Default")
      (node (ref "J8") (pin "3") (pinfunction "3_3") (pintype "passive"))
      (node (ref "R30") (pin "1") (pinfunction "1_1") (pintype "passive"))
      (node (ref "U6") (pin "19") (pinfunction "PA15/PA14-BOOT0_19") (pintype "bidirectional"))
    )
    (net (code "22") (name "/SWDIO") (class "Default")
      (node (ref "J8") (pin "2") (pinfunction "2_2") (pintype "passive"))
      (node (ref "U6") (pin "18") (pinfunction "PA13_18") (pintype "bidirectional"))
    )
    (net (code "23") (name "/TX") (class "Default")
      (node (ref "J8") (pin "4") (pinfunction "4_4") (pintype "passive"))
      (node (ref "R40") (pin "1") (pinfunction "1_1") (pintype "passive"))
      (node (ref "TP26") (pin "1") (pinfunction "G9_1") (pintype "passive"))
      (node (ref "U10") (pin "4") (pinfunction "VIB_4") (pintype "input"))
      (node (ref "U6") (pin "20") (pinfunction "PB3/PB4/PB5/PB6_20") (pintype "bidirectional"))
    )
    (net (code "25") (name "GND_2") (class "Default")
      (node (ref "C36") (pin "2") (pinfunction "2_2") (pintype "passive"))
      (node (ref "R46") (pin "1") (pinfunction "1_1") (pintype "passive"))
      (node (ref "R49") (pin "1") (pinfunction "1_1") (pintype "passive"))
      (node (ref "TP30") (pin "1") (pinfunction "G9_1") (pintype "passive"))
      (node (ref "U10") (pin "15") (pinfunction "GND2_15") (pintype "power_in"))
      (node (ref "U10") (pin "9") (pinfunction "GND2_9") (pintype "power_in"))
      (node (ref "U8") (pin "3") (pinfunction "0V_3") (pintype "power_in"))
      (node (ref "U9") (pin "5") (pinfunction "GND_5") (pintype "power_in"))
      (node (ref "X4") (pin "2") (pinfunction "2_2") (pintype "passive"))
      (node (ref "ZD2") (pin "1") (pinfunction "A_1") (pintype "passive"))
      (node (ref "ZD3") (pin "1") (pinfunction "A_1") (pintype "passive"))
    )
    (net (code "26") (name "GND_III") (class "Default")
      (node (ref "C1") (pin "1") (pinfunction "1_1") (pintype "passive"))
      (node (ref "C10") (pin "2") (pinfunction "-_2") (pintype "passive"))
      (node (ref "C11") (pin "2") (pinfunction "-_2") (pintype "passive"))
      (node (ref "C12") (pin "2") (pinfunction "-_2") (pintype "passive"))
      (node (ref "C13") (pin "1") (pinfunction "1_1") (pintype "passive"))
      (node (ref "C14") (pin "1") (pinfunction "1_1") (pintype "passive"))
      (node (ref "C18") (pin "1") (pinfunction "1_1") (pintype "passive"))
      (node (ref "C19") (pin "1") (pinfunction "1_1") (pintype "passive"))
      (node (ref "C2") (pin "1") (pinfunction "1_1") (pintype "passive"))
      (node (ref "C21") (pin "1") (pinfunction "1_1") (pintype "passive"))
      (node (ref "C25") (pin "1") (pinfunction "1_1") (pintype "passive"))
      (node (ref "C26") (pin "1") (pinfunction "1_1") (pintype "passive"))
      (node (ref "C27") (pin "2") (pinfunction "2_2") (pintype "passive"))
      (node (ref "C3") (pin "2") (pinfunction "-_2") (pintype "passive"))
      (node (ref "C30") (pin "1") (pinfunction "1_1") (pintype "passive"))
      (node (ref "C31") (pin "1") (pinfunction "1_1") (pintype "passive"))
      (node (ref "C32") (pin "2") (pinfunction "2_2") (pintype "passive"))
      (node (ref "C34") (pin "1") (pinfunction "1_1") (pintype "passive"))
      (node (ref "C37") (pin "1") (pinfunction "1_1") (pintype "passive"))
      (node (ref "C38") (pin "1") (pinfunction "1_1") (pintype "passive"))
      (node (ref "C39") (pin "1") (pinfunction "1_1") (pintype "passive"))
      (node (ref "C4") (pin "2") (pinfunction "-_2") (pintype "passive"))
      (node (ref "C5") (pin "2") (pinfunction "-_2") (pintype "passive"))
      (node (ref "C6") (pin "1") (pinfunction "1_1") (pintype "passive"))
      (node (ref "C7") (pin "1") (pinfunction "1_1") (pintype "passive"))
      (node (ref "C8") (pin "1") (pinfunction "1_1") (pintype "passive"))
      (node (ref "C9") (pin "2") (pinfunction "-_2") (pintype "passive"))
      (node (ref "D10") (pin "2") (pinfunction "A_2") (pintype "passive"))
      (node (ref "D11") (pin "2") (pinfunction "A_2") (pintype "passive"))
      (node (ref "D12") (pin "2") (pinfunction "A_2") (pintype "passive"))
      (node (ref "D13") (pin "2") (pinfunction "K_2") (pintype "passive"))
      (node (ref "D2") (pin "2") (pinfunction "A_2") (pintype "passive"))
      (node (ref "D3") (pin "2") (pinfunction "K_2") (pintype "passive"))
      (node (ref "D4") (pin "2") (pinfunction "K_2") (pintype "passive"))
      (node (ref "D6") (pin "2") (pinfunction "A_2") (pintype "passive"))
      (node (ref "J11") (pin "2") (pinfunction "2_2") (pintype "passive"))
      (node (ref "J12") (pin "2") (pinfunction "2_2") (pintype "passive"))
      (node (ref "J13") (pin "2") (pinfunction "2_2") (pintype "passive"))
      (node (ref "J3") (pin "1") (pinfunction "1_1") (pintype "passive"))
      (node (ref "J8") (pin "6") (pinfunction "6_6") (pintype "passive"))
      (node (ref "J9") (pin "2") (pinfunction "2_2") (pintype "passive"))
      (node (ref "R1") (pin "2") (pinfunction "2_2") (pintype "passive"))
      (node (ref "R16") (pin "2") (pinfunction "2_2") (pintype "passive"))
      (node (ref "R2") (pin "1") (pinfunction "1_1") (pintype "passive"))
      (node (ref "R20") (pin "1") (pinfunction "1_1") (pintype "passive"))
      (node (ref "R30") (pin "2") (pinfunction "2_2") (pintype "passive"))
      (node (ref "R32") (pin "1") (pinfunction "1_1") (pintype "passive"))
      (node (ref "R34") (pin "1") (pinfunction "1_1") (pintype "passive"))
      (node (ref "R48") (pin "1") (pinfunction "1_1") (pintype "passive"))
      (node (ref "TP21") (pin "1") (pinfunction "G9_1") (pintype "passive"))
      (node (ref "TP4") (pin "1") (pinfunction "G9_1") (pintype "passive"))
      (node (ref "U1") (pin "3") (pinfunction "SD_3") (pintype "input"))
      (node (ref "U1") (pin "4") (pinfunction "GND_4") (pintype "power_in"))
      (node (ref "U10") (pin "2") (pinfunction "GND1_2") (pintype "power_in"))
      (node (ref "U10") (pin "8") (pinfunction "GND1_8") (pintype "power_in"))
      (node (ref "U2") (pin "1") (pinfunction "Ground_1") (pintype "power_in"))
      (node (ref "U3") (pin "1") (pinfunction "Ground_1") (pintype "power_in"))
      (node (ref "U5") (pin "2") (pinfunction "VSS_2") (pintype "power_in"))
      (node (ref "U6") (pin "5") (pinfunction "VSS/VSSA_5") (pintype "power_in"))
      (node (ref "U7") (pin "4") (pinfunction "GND_4") (pintype "power_in"))
      (node (ref "U8") (pin "1") (pinfunction "GND_1") (pintype "power_in"))
      (node (ref "VD1") (pin "1") (pinfunction "A_1") (pintype "passive"))
      (node (ref "VD2") (pin "1") (pinfunction "A_1") (pintype "passive"))
      (node (ref "X1") (pin "1") (pinfunction "1_1") (pintype "passive"))
      (node (ref "X1") (pin "2") (pinfunction "2_2") (pintype "passive"))
      (node (ref "X1") (pin "4") (pinfunction "4_4") (pintype "passive"))
      (node (ref "X2") (pin "1") (pinfunction "1_1") (pintype "passive"))
      (node (ref "X2") (pin "2") (pinfunction "2_2") (pintype "passive"))
      (node (ref "X3") (pin "2") (pinfunction "2_2") (pintype "passive"))
      (node (ref "X3") (pin "3") (pinfunction "3_3") (pintype "passive"))
      (node (ref "X5") (pin "1") (pinfunction "1_1") (pintype "passive"))
    )
    (net (code "27") (name "Net-(C4-+)") (class "Default")
      (node (ref "C30") (pin "2") (pinfunction "2_2") (pintype "passive"))
      (node (ref "C4") (pin "1") (pinfunction "+_1") (pintype "passive"))
      (node (ref "L3") (pin "2") (pinfunction "2_2") (pintype "passive"))
      (node (ref "TP19") (pin "1") (pinfunction "G9_1") (pintype "passive"))
      (node (ref "U3") (pin "3") (pinfunction "VIN_3") (pintype "power_in"))
    )
    (net (code "28") (name "Net-(C9-+)") (class "Default")
      (node (ref "C9") (pin "1") (pinfunction "+_1") (pintype "passive"))
      (node (ref "JE1") (pin "1") (pinfunction "1_1") (pintype "passive"))
      (node (ref "L3") (pin "1") (pinfunction "1_1") (pintype "passive"))
      (node (ref "U1") (pin "8") (pinfunction "IN_8") (pintype "power_in"))
    )
    (net (code "29") (name "Net-(C10-+)") (class "Default")
      (node (ref "C10") (pin "1") (pinfunction "+_1") (pintype "passive"))
      (node (ref "JE1") (pin "2") (pinfunction "2_2") (pintype "passive"))
      (node (ref "L2") (pin "2") (pinfunction "2_2") (pintype "passive"))
      (node (ref "R33") (pin "1") (pinfunction "1_1") (pintype "passive"))
    )
    (net (code "30") (name "Net-(C18-Pad2)") (class "Default")
      (node (ref "C18") (pin "2") (pinfunction "2_2") (pintype "passive"))
      (node (ref "R12") (pin "1") (pinfunction "1_1") (pintype "passive"))
      (node (ref "R13") (pin "2") (pinfunction "2_2") (pintype "passive"))
    )
    (net (code "31") (name "Net-(D1-A)") (class "Default")
      (node (ref "D1") (pin "1") (pinfunction "A_1") (pintype "passive"))
      (node (ref "R25") (pin "1") (pinfunction "1_1") (pintype "passive"))
    )
    (net (code "32") (name "Net-(D2-C)") (class "Default")
      (node (ref "D2") (pin "1") (pinfunction "C_1") (pintype "passive"))
      (node (ref "L2") (pin "1") (pinfunction "1_1") (pintype "passive"))
      (node (ref "TP18") (pin "1") (pinfunction "G9_1") (pintype "passive"))
      (node (ref "U7") (pin "2") (pinfunction "SWE_2") (pintype "open_emitter"))
    )
    (net (code "33") (name "Net-(D3-A)") (class "Default")
      (node (ref "D3") (pin "1") (pinfunction "A_1") (pintype "passive"))
      (node (ref "R27") (pin "2") (pinfunction "2_2") (pintype "passive"))
    )
    (net (code "34") (name "Net-(D4-A)") (class "Default")
      (node (ref "D4") (pin "1") (pinfunction "A_1") (pintype "passive"))
      (node (ref "R31") (pin "2") (pinfunction "2_2") (pintype "passive"))
    )
    (net (code "35") (name "Net-(D13-A)") (class "Default")
      (node (ref "D13") (pin "1") (pinfunction "A_1") (pintype "passive"))
      (node (ref "R47") (pin "1") (pinfunction "1_1") (pintype "passive"))
    )
    (net (code "36") (name "Net-(J3-Pad3)") (class "Default")
      (node (ref "J3") (pin "3") (pinfunction "3_3") (pintype "passive"))
      (node (ref "R7") (pin "2") (pinfunction "2_2") (pintype "passive"))
    )
    (net (code "37") (name "Net-(J3-Pad4)") (class "Default")
      (node (ref "J3") (pin "4") (pinfunction "4_4") (pintype "passive"))
      (node (ref "R10") (pin "2") (pinfunction "2_2") (pintype "passive"))
    )
    (net (code "38") (name "Net-(TP10-G9)") (class "Default")
      (node (ref "C16") (pin "2") (pinfunction "2_2") (pintype "passive"))
      (node (ref "C21") (pin "2") (pinfunction "2_2") (pintype "passive"))
      (node (ref "R11") (pin "2") (pinfunction "2_2") (pintype "passive"))
      (node (ref "R20") (pin "2") (pinfunction "2_2") (pintype "passive"))
      (node (ref "TP10") (pin "1") (pinfunction "G9_1") (pintype "passive"))
      (node (ref "U5") (pin "3") (pinfunction "VIN+_3") (pintype "input"))
    )
    (net (code "39") (name "Net-(TP11-G9)") (class "Default")
      (node (ref "C19") (pin "2") (pinfunction "2_2") (pintype "passive"))
      (node (ref "R13") (pin "1") (pinfunction "1_1") (pintype "passive"))
      (node (ref "R14") (pin "2") (pinfunction "2_2") (pintype "passive"))
      (node (ref "R16") (pin "1") (pinfunction "1_1") (pintype "passive"))
      (node (ref "TP11") (pin "1") (pinfunction "G9_1") (pintype "passive"))
    )
    (net (code "40") (name "Net-(TP12-G9)") (class "Default")
      (node (ref "C22") (pin "2") (pinfunction "2_2") (pintype "passive"))
      (node (ref "R12") (pin "2") (pinfunction "2_2") (pintype "passive"))
      (node (ref "R21") (pin "2") (pinfunction "2_2") (pintype "passive"))
      (node (ref "TP12") (pin "1") (pinfunction "G9_1") (pintype "passive"))
      (node (ref "U5") (pin "1") (pinfunction "VOUT_1") (pintype "output"))
    )
    (net (code "41") (name "Net-(TP14-G9)") (class "Default")
      (node (ref "C16") (pin "1") (pinfunction "1_1") (pintype "passive"))
      (node (ref "C22") (pin "1") (pinfunction "1_1") (pintype "passive"))
      (node (ref "R15") (pin "2") (pinfunction "2_2") (pintype "passive"))
      (node (ref "R21") (pin "1") (pinfunction "1_1") (pintype "passive"))
      (node (ref "TP14") (pin "1") (pinfunction "G9_1") (pintype "passive"))
      (node (ref "U5") (pin "4") (pinfunction "VIN-_4") (pintype "input"))
    )
    (net (code "42") (name "Net-(TP24-G9)") (class "Default")
      (node (ref "R38") (pin "1") (pinfunction "1_1") (pintype "passive"))
      (node (ref "R41") (pin "1") (pinfunction "1_1") (pintype "passive"))
      (node (ref "TP24") (pin "1") (pinfunction "G9_1") (pintype "passive"))
      (node (ref "U9") (pin "4") (pinfunction "DI_4") (pintype "input"))
    )
    (net (code "43") (name "Net-(TP27-G9)") (class "Default")
      (node (ref "R46") (pin "2") (pinfunction "2_2") (pintype "passive"))
      (node (ref "TP27") (pin "1") (pinfunction "G9_1") (pintype "passive"))
      (node (ref "U10") (pin "12") (pinfunction "VOC_12") (pintype "tri_state"))
      (node (ref "U9") (pin "2") (pinfunction "~{RE}_2") (pintype "input"))
      (node (ref "U9") (pin "3") (pinfunction "DE_3") (pintype "input"))
    )
    (net (code "44") (name "Net-(TP29-G9)") (class "Default")
      (node (ref "R39") (pin "1") (pinfunction "1_1") (pintype "passive"))
      (node (ref "R45") (pin "1") (pinfunction "1_1") (pintype "passive"))
      (node (ref "TP29") (pin "1") (pinfunction "G9_1") (pintype "passive"))
      (node (ref "U9") (pin "1") (pinfunction "RO_1") (pintype "output"))
    )
    (net (code "45") (name "Net-(U1-FB)") (class "Default")
      (node (ref "U1") (pin "6") (pinfunction "VTAP_6") (pintype "passive"))
      (node (ref "U1") (pin "7") (pinfunction "FB_7") (pintype "input"))
    )
    (net (code "46") (name "Net-(U1-~{ERR})") (class "Default")
      (node (ref "R3") (pin "2") (pinfunction "2_2") (pintype "passive"))
      (node (ref "U1") (pin "5") (pinfunction "~{ERR}_5") (pintype "open_collector"))
    )
    (net (code "47") (name "Net-(U6-PA7)") (class "Default")
      (node (ref "R27") (pin "1") (pinfunction "1_1") (pintype "passive"))
      (node (ref "U6") (pin "14") (pinfunction "PA7_14") (pintype "bidirectional"))
    )
    (net (code "48") (name "Net-(U6-PC15-OSC32_OUT)") (class "Default")
      (node (ref "R31") (pin "1") (pinfunction "1_1") (pintype "passive"))
      (node (ref "U6") (pin "3") (pinfunction "PC15-OSC32_OUT_3") (pintype "bidirectional"))
    )
    (net (code "49") (name "Net-(U6-~{RST})") (class "Default")
      (node (ref "C26") (pin "2") (pinfunction "2_2") (pintype "passive"))
      (node (ref "R26") (pin "2") (pinfunction "2_2") (pintype "passive"))
      (node (ref "U6") (pin "6") (pinfunction "~{RST}_6") (pintype "input"))
    )
    (net (code "50") (name "Net-(U7-CII)") (class "Default")
      (node (ref "R33") (pin "2") (pinfunction "2_2") (pintype "passive"))
      (node (ref "R34") (pin "2") (pinfunction "2_2") (pintype "passive"))
      (node (ref "U7") (pin "5") (pinfunction "CII_5") (pintype "input"))
    )
    (net (code "51") (name "Net-(U7-DRC)") (class "Default")
      (node (ref "R28") (pin "2") (pinfunction "2_2") (pintype "passive"))
      (node (ref "U7") (pin "1") (pinfunction "SWC_1") (pintype "open_collector"))
      (node (ref "U7") (pin "7") (pinfunction "IPK_7") (pintype "passive"))
      (node (ref "U7") (pin "8") (pinfunction "DRC_8") (pintype "open_collector"))
    )
    (net (code "52") (name "Net-(U7-TC)") (class "Default")
      (node (ref "C27") (pin "1") (pinfunction "1_1") (pintype "passive"))
      (node (ref "U7") (pin "3") (pinfunction "TC_3") (pintype "passive"))
    )
    (net (code "53") (name "Net-(U9-A)") (class "Default")
      (node (ref "R36") (pin "1") (pinfunction "1_1") (pintype "passive"))
      (node (ref "U9") (pin "6") (pinfunction "A_6") (pintype "bidirectional"))
      (node (ref "X4") (pin "3") (pinfunction "3_3") (pintype "passive"))
      (node (ref "ZD1") (pin "2") (pinfunction "A_2") (pintype "passive"))
      (node (ref "ZD2") (pin "2") (pinfunction "A_2") (pintype "passive"))
    )
    (net (code "54") (name "Net-(U9-B)") (class "Default")
      (node (ref "R49") (pin "2") (pinfunction "2_2") (pintype "passive"))
      (node (ref "U9") (pin "7") (pinfunction "B_7") (pintype "bidirectional"))
      (node (ref "X4") (pin "1") (pinfunction "1_1") (pintype "passive"))
      (node (ref "ZD1") (pin "1") (pinfunction "A_1") (pintype "passive"))
      (node (ref "ZD3") (pin "2") (pinfunction "A_2") (pintype "passive"))
    )
    (net (code "55") (name "Net-(U10-VID)") (class "Default")
      (node (ref "R45") (pin "2") (pinfunction "2_2") (pintype "passive"))
      (node (ref "U10") (pin "11") (pinfunction "VID_11") (pintype "input"))
    )
    (net (code "56") (name "Net-(U10-VOB)") (class "Default")
      (node (ref "R41") (pin "2") (pinfunction "2_2") (pintype "passive"))
      (node (ref "U10") (pin "13") (pinfunction "VOB_13") (pintype "tri_state"))
    )
    (net (code "57") (name "VCC") (class "Default")
      (node (ref "C12") (pin "1") (pinfunction "+_1") (pintype "passive"))
      (node (ref "C32") (pin "1") (pinfunction "1_1") (pintype "passive"))
      (node (ref "R28") (pin "1") (pinfunction "1_1") (pintype "passive"))
      (node (ref "U7") (pin "6") (pinfunction "VCC_6") (pintype "power_in"))
      (node (ref "X3") (pin "4") (pinfunction "4_4") (pintype "passive"))
      (node (ref "X3") (pin "5") (pinfunction "5_5") (pintype "passive"))
      (node (ref "X5") (pin "2") (pinfunction "2_2") (pintype "passive"))
    )
    (net (code "58") (name "unconnected-(DD1-GND-Pad1)") (class "Default")
      (node (ref "DD1") (pin "1") (pinfunction "GND_1") (pintype "passive"))
    )
    (net (code "59") (name "unconnected-(DD1-SCL-Pad3)") (class "Default")
      (node (ref "DD1") (pin "3") (pinfunction "SCL_3") (pintype "passive"))
    )
    (net (code "60") (name "unconnected-(DD1-SDA-Pad4)") (class "Default")
      (node (ref "DD1") (pin "4") (pinfunction "SDA_4") (pintype "passive"))
    )
    (net (code "61") (name "unconnected-(DD1-VCC-Pad2)") (class "Default")
      (node (ref "DD1") (pin "2") (pinfunction "VCC_2") (pintype "passive"))
    )
    (net (code "62") (name "unconnected-(U10-VIA-Pad3)") (class "Default")
      (node (ref "U10") (pin "3") (pinfunction "VIA_3") (pintype "input"))
    )
    (net (code "63") (name "unconnected-(U10-VOA-Pad14)") (class "Default")
      (node (ref "U10") (pin "14") (pinfunction "VOA_14") (pintype "tri_state"))
    )
  )
)
